# 08_Power_Supply.net
KiCad netlist of a schematic drawn in Altium Designer
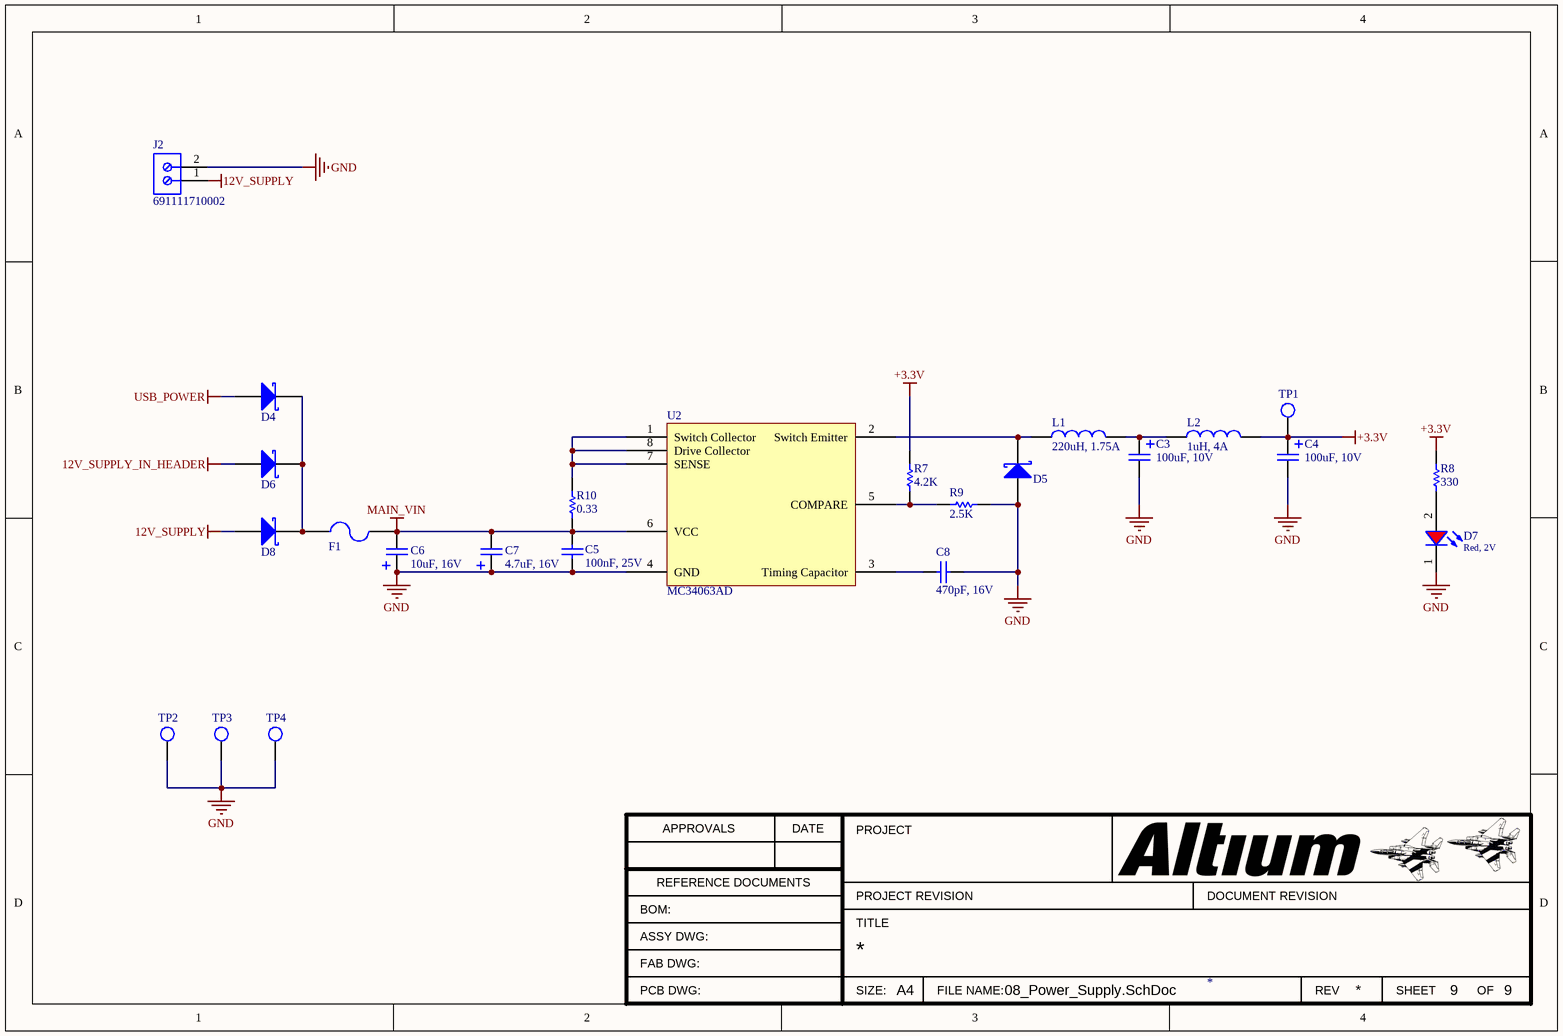
[diagram p0: 08_Power_Supply.SchDoc]

(export (version "E")
  (design (tool "Eeschema 10.0.6"))
  (components
    (comp (ref "C3")
      (value "100uF, 10V")
      (footprint "TAN1210")
      (fields (field (name "Comment") "Tantalum Capacitor"))
      (libsource (lib "MiclsLib") (part "Tantalum Capacitor"))
    )
    (comp (ref "C4")
      (value "100uF, 10V")
      (footprint "TAN1210")
      (fields (field (name "Comment") "Tantalum Capacitor"))
      (libsource (lib "MiclsLib") (part "Tantalum Capacitor"))
    )
    (comp (ref "C5")
      (value "100nF, 25V")
      (footprint "WCAP-CSGP_0603_H=0.8mm_Reflow")
      (description "WCAP-CSGP Multilayer Ceramic Chip Capacitor, General Purpose, size 0603, X7R, 100nF, 25V")
      (fields
        (field (name "MANUFACTURER PART NUMBER") "885012206071")
        (field (name "MANUFACTURER") "Wurth Elektronik")
      )
      (libsource (lib "Altium_WCAP-CSGP (rev20a)") (part "885012206071"))
    )
    (comp (ref "C6")
      (value "10uF, 16V")
      (footprint "TAN1206")
      (fields (field (name "Comment") "Tantalum Capacitor"))
      (libsource (lib "MiclsLib") (part "Tantalum Capacitor"))
    )
    (comp (ref "C7")
      (value "4.7uF, 16V")
      (footprint "TAN1206")
      (fields (field (name "Comment") "Tantalum Capacitor"))
      (libsource (lib "MiclsLib") (part "Tantalum Capacitor"))
    )
    (comp (ref "C8")
      (value "470pF, 16V")
      (footprint "WCAP-CSGP_0603_H=0.8mm_Reflow")
      (description "WCAP-CSGP Multilayer Ceramic Chip Capacitor, General Purpose, size 0603, NP0, 470pF, 16V")
      (fields
        (field (name "MANUFACTURER PART NUMBER") "885012006027")
        (field (name "MANUFACTURER") "Wurth Elektronik")
      )
      (libsource (lib "Altium_WCAP-CSGP (rev20a)") (part "885012006027"))
    )
    (comp (ref "D4")
      (value "D Schottky")
      (footprint "SS34")
      (description "Schottky Diode")
      (fields (field (name "PUBLISHER") "Altium Limited"))
      (libsource (lib "PIF_Library") (part "D Schottky"))
    )
    (comp (ref "D5")
      (value "D Schottky")
      (footprint "SS34")
      (description "Schottky Diode")
      (fields (field (name "PUBLISHER") "Altium Limited"))
      (libsource (lib "PIF_Library") (part "D Schottky"))
    )
    (comp (ref "D6")
      (value "D Schottky")
      (footprint "SS34")
      (description "Schottky Diode")
      (fields (field (name "PUBLISHER") "Altium Limited"))
      (libsource (lib "PIF_Library") (part "D Schottky"))
    )
    (comp (ref "D7")
      (value "Red, 2V")
      (footprint "WL-SMCW_0603_H=0.7mm")
      (description "WL-SMCW SMT Mono-color Chip LED Waterclear, size 0603, Red, 2V, 140deg")
      (fields (field (name "PART NUMBER") "150060RS75000") (field (name "PUBLISHER") "Wurth Elektronik"))
      (libsource (lib "Altium_WL-SMCW (rev20a)") (part "150060RS75000"))
    )
    (comp (ref "D8")
      (value "D Schottky")
      (footprint "SS34")
      (description "Schottky Diode")
      (fields (field (name "PUBLISHER") "Altium Limited"))
      (libsource (lib "PIF_Library") (part "D Schottky"))
    )
    (comp (ref "F1") (value "Fuse") (footprint "FUSE SMD") (libsource (lib "PIF_Library") (part "Fuse")))
    (comp (ref "J2")
      (value "691111710002")
      (footprint "691111710002")
      (description "WR-TBL Serie 111 Horizontal Entry Modular, Pressure Clamp, pitch 5mm, 2p")
      (fields (field (name "PUBLISHER") "Wurth Elektronik"))
      (libsource (lib "691322310002.") (part "691111710002"))
    )
    (comp (ref "L1")
      (value "220uH, 1.75A")
      (footprint "WE-PD2A_5848")
      (description "WE-PD2A SMT Power Inductor, size 5848, 220uH, 0.41A")
      (fields
        (field (name "MANUFACTURER PART NUMBER") "784774222")
        (field (name "MANUFACTURER") "Wurth Elektronik")
      )
      (libsource (lib "Altium_WE-PD2A (rev20a)") (part "784774222"))
    )
    (comp (ref "L2")
      (value "1uH, 4A")
      (footprint "WE-PD2A_4532")
      (description "WE-PD2A SMT Power Inductor, size 4532, 1uH, 4A")
      (fields
        (field (name "MANUFACTURER PART NUMBER") "7847730")
        (field (name "MANUFACTURER") "Wurth Elektronik")
      )
      (libsource (lib "Altium_WE-PD2A (rev20a)") (part "7847730"))
    )
    (comp (ref "R7")
      (value "4.2K")
      (footprint "RES-SM-0603")
      (description "Resistor")
      (fields (field (name "Comment") "RESISTOR SMD"))
      (libsource (lib "PIF_Library") (part "RESISTOR SMD"))
    )
    (comp (ref "R8")
      (value "330")
      (footprint "RES-SM-0603")
      (description "Resistor")
      (fields (field (name "Comment") "RESISTOR SMD"))
      (libsource (lib "PIF_Library") (part "RESISTOR SMD"))
    )
    (comp (ref "R9")
      (value "2.5K")
      (footprint "RES-SM-0603")
      (description "Resistor")
      (fields (field (name "Comment") "RESISTOR SMD"))
      (libsource (lib "PIF_Library") (part "RESISTOR SMD"))
    )
    (comp (ref "R10")
      (value "0.33")
      (footprint "RES-SM-0805")
      (description "Resistor")
      (fields (field (name "Comment") "RESISTOR SMD"))
      (libsource (lib "PIF_Library") (part "RESISTOR SMD"))
    )
    (comp (ref "TP1") (value "Test point") (footprint "TP") (libsource (lib "MiclsLib") (part "TP")))
    (comp (ref "TP2") (value "Test point") (footprint "TP") (libsource (lib "MiclsLib") (part "TP")))
    (comp (ref "TP3") (value "Test point") (footprint "TP") (libsource (lib "MiclsLib") (part "TP")))
    (comp (ref "TP4") (value "Test point") (footprint "TP") (libsource (lib "MiclsLib") (part "TP")))
    (comp (ref "U2")
      (value "MC34063AD")
      (footprint "SOIC127P600X170-8N")
      (description "1.5-A boost, buck, inverting switching regulator, operation from 0°C to 70°C")
      (fields (field (name "MANUFACTURER") "Texas Instruments"))
      (libsource (lib "PowerSupply") (part "MC34063"))
    )
  )
  (nets
    (net (code "1") (name "+3.3V") (class "Default")
      (node (ref "C4") (pin "1") (pinfunction "1_1") (pintype "passive"))
      (node (ref "L2") (pin "2") (pinfunction "2_2") (pintype "passive"))
      (node (ref "R7") (pin "2") (pinfunction "2_2") (pintype "passive"))
      (node (ref "R8") (pin "2") (pinfunction "2_2") (pintype "passive"))
      (node (ref "TP1") (pin "1") (pinfunction "27_1") (pintype "passive"))
    )
    (net (code "2") (name "12V_SUPPLY") (class "Default")
      (node (ref "D8") (pin "1") (pinfunction "A_1") (pintype "passive"))
      (node (ref "J2") (pin "1") (pinfunction "1_1") (pintype "passive"))
    )
    (net (code "3") (name "12V_SUPPLY_IN_HEADER") (class "Default")
      (node (ref "D6") (pin "1") (pinfunction "A_1") (pintype "passive"))
    )
    (net (code "4") (name "GND") (class "Default")
      (node (ref "C3") (pin "2") (pinfunction "2_2") (pintype "passive"))
      (node (ref "C4") (pin "2") (pinfunction "2_2") (pintype "passive"))
      (node (ref "C5") (pin "1") (pinfunction "1_1") (pintype "passive"))
      (node (ref "C6") (pin "1") (pinfunction "1_1") (pintype "passive"))
      (node (ref "C7") (pin "1") (pinfunction "1_1") (pintype "passive"))
      (node (ref "C8") (pin "2") (pinfunction "2_2") (pintype "passive"))
      (node (ref "D5") (pin "1") (pinfunction "A_1") (pintype "passive"))
      (node (ref "D7") (pin "1") (pinfunction "K_1") (pintype "passive"))
      (node (ref "J2") (pin "2") (pinfunction "2_2") (pintype "passive"))
      (node (ref "R9") (pin "1") (pinfunction "1_1") (pintype "passive"))
      (node (ref "TP2") (pin "1") (pinfunction "27_1") (pintype "passive"))
      (node (ref "TP3") (pin "1") (pinfunction "27_1") (pintype "passive"))
      (node (ref "TP4") (pin "1") (pinfunction "27_1") (pintype "passive"))
      (node (ref "U2") (pin "4") (pinfunction "GND_4") (pintype "passive"))
    )
    (net (code "5") (name "MAIN_VIN") (class "Default")
      (node (ref "C5") (pin "2") (pinfunction "2_2") (pintype "passive"))
      (node (ref "C6") (pin "2") (pinfunction "2_2") (pintype "passive"))
      (node (ref "C7") (pin "2") (pinfunction "2_2") (pintype "passive"))
      (node (ref "F1") (pin "2") (pinfunction "2_2") (pintype "passive"))
      (node (ref "R10") (pin "1") (pinfunction "1_1") (pintype "passive"))
      (node (ref "U2") (pin "6") (pinfunction "VCC_6") (pintype "passive"))
    )
    (net (code "6") (name "Net-(C3-Pad1)") (class "Default")
      (node (ref "C3") (pin "1") (pinfunction "1_1") (pintype "passive"))
      (node (ref "L1") (pin "2") (pinfunction "2_2") (pintype "passive"))
      (node (ref "L2") (pin "1") (pinfunction "1_1") (pintype "passive"))
    )
    (net (code "7") (name "Net-(D4-K)") (class "Default")
      (node (ref "D4") (pin "2") (pinfunction "K_2") (pintype "passive"))
      (node (ref "D6") (pin "2") (pinfunction "K_2") (pintype "passive"))
      (node (ref "D8") (pin "2") (pinfunction "K_2") (pintype "passive"))
      (node (ref "F1") (pin "1") (pinfunction "1_1") (pintype "passive"))
    )
    (net (code "8") (name "Net-(D5-K)") (class "Default")
      (node (ref "D5") (pin "2") (pinfunction "K_2") (pintype "passive"))
      (node (ref "L1") (pin "1") (pinfunction "1_1") (pintype "passive"))
      (node (ref "U2") (pin "2") (pinfunction "Switch_Emitter_2") (pintype "passive"))
    )
    (net (code "9") (name "Net-(D7-A)") (class "Default")
      (node (ref "D7") (pin "2") (pinfunction "A_2") (pintype "passive"))
      (node (ref "R8") (pin "1") (pinfunction "1_1") (pintype "passive"))
    )
    (net (code "10") (name "Net-(U2-COMPARE)") (class "Default")
      (node (ref "R7") (pin "1") (pinfunction "1_1") (pintype "passive"))
      (node (ref "R9") (pin "2") (pinfunction "2_2") (pintype "passive"))
      (node (ref "U2") (pin "5") (pinfunction "COMPARE_5") (pintype "passive"))
    )
    (net (code "11") (name "Net-(U2-Drive_Collector)") (class "Default")
      (node (ref "R10") (pin "2") (pinfunction "2_2") (pintype "passive"))
      (node (ref "U2") (pin "1") (pinfunction "Switch_Collector_1") (pintype "passive"))
      (node (ref "U2") (pin "7") (pinfunction "SENSE_7") (pintype "passive"))
      (node (ref "U2") (pin "8") (pinfunction "Drive_Collector_8") (pintype "passive"))
    )
    (net (code "12") (name "Net-(U2-Timing_Capacitor)") (class "Default")
      (node (ref "C8") (pin "1") (pinfunction "1_1") (pintype "passive"))
      (node (ref "U2") (pin "3") (pinfunction "Timing_Capacitor_3") (pintype "passive"))
    )
    (net (code "13") (name "USB_POWER") (class "Default")
      (node (ref "D4") (pin "1") (pinfunction "A_1") (pintype "passive"))
    )
  )
)
